# Sheet_Autolabor_Power.net
KiCad netlist of a schematic drawn in Altium Designer
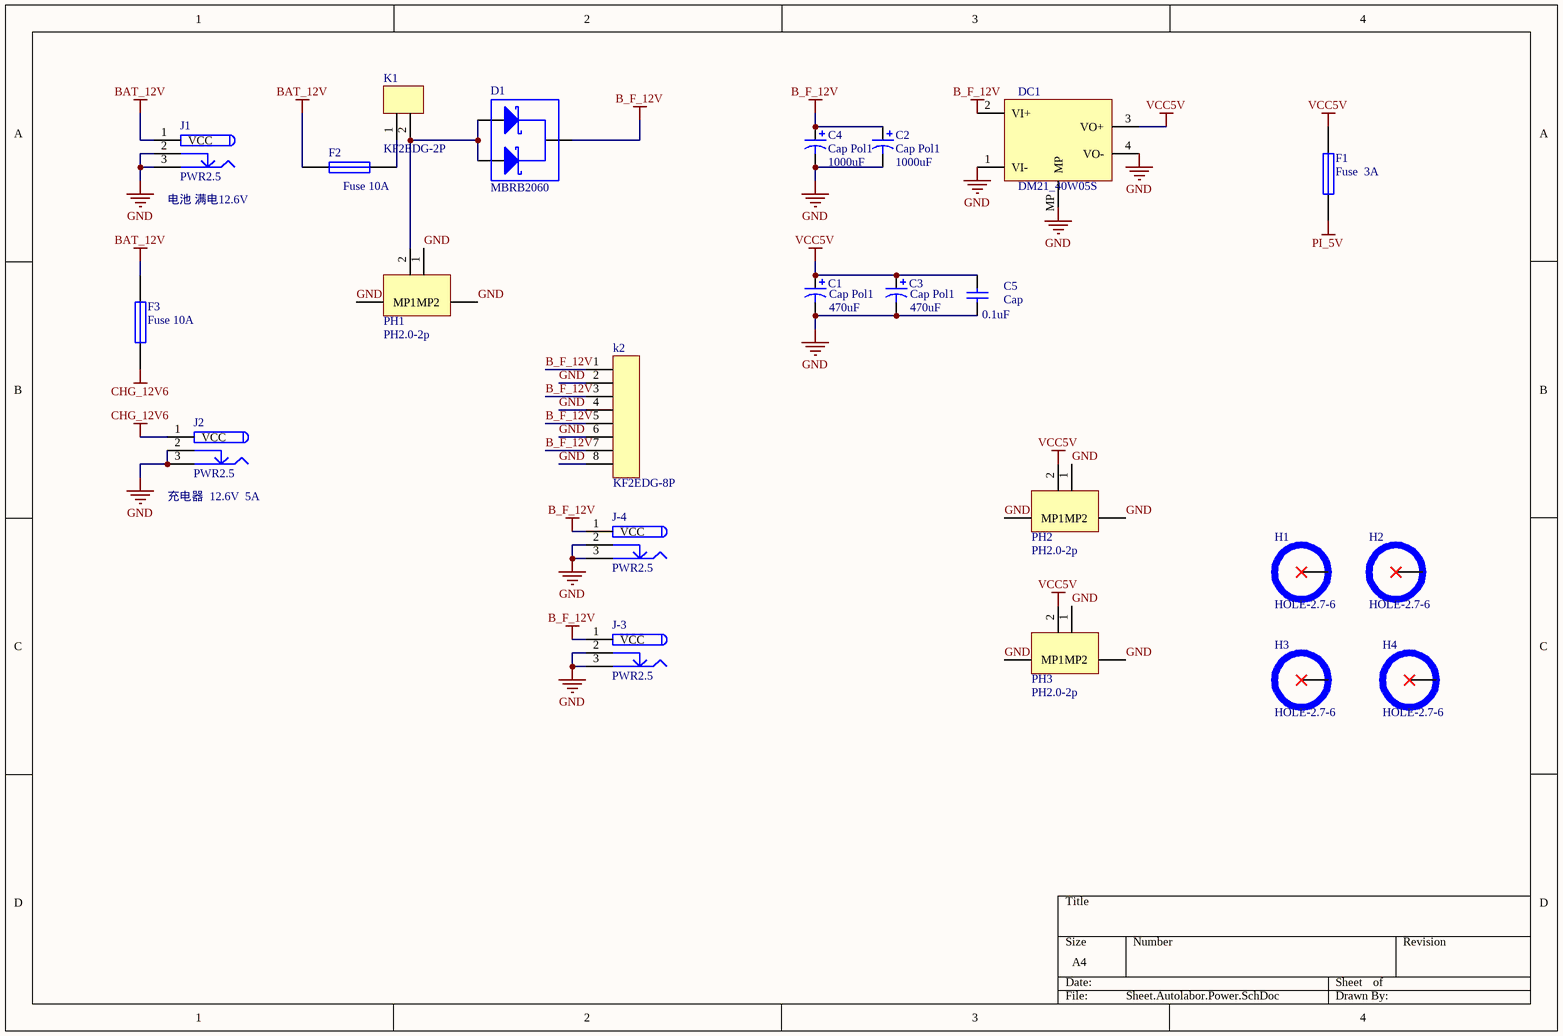
[diagram p0: Sheet.Autolabor.Power.SchDoc]

(export (version "E")
  (design (tool "Eeschema 10.0.6"))
  (components
    (comp (ref "C1")
      (value "Cap Pol1")
      (footprint "CAPAE8883X102M")
      (description "Polarized Capacitor (Radial)")
      (fields (field (name "ALTIUM_VALUE") "470uF") (field (name "PUBLISHER") "Altium Limited"))
      (libsource (lib "Miscellaneous Devices") (part "Cap Pol1"))
    )
    (comp (ref "C2")
      (value "Cap Pol1")
      (footprint "CAPAE108103X102M")
      (description "Polarized Capacitor (Radial)")
      (fields (field (name "ALTIUM_VALUE") "1000uF") (field (name "PUBLISHER") "Altium Limited"))
      (libsource (lib "Miscellaneous Devices") (part "Cap Pol1"))
    )
    (comp (ref "C3")
      (value "Cap Pol1")
      (footprint "CAPAE8883X102M")
      (description "Polarized Capacitor (Radial)")
      (fields (field (name "ALTIUM_VALUE") "470uF") (field (name "PUBLISHER") "Altium Limited"))
      (libsource (lib "Miscellaneous Devices") (part "Cap Pol1"))
    )
    (comp (ref "C4")
      (value "Cap Pol1")
      (footprint "CAPAE108103X102M")
      (description "Polarized Capacitor (Radial)")
      (fields (field (name "ALTIUM_VALUE") "1000uF") (field (name "PUBLISHER") "Altium Limited"))
      (libsource (lib "Miscellaneous Devices") (part "Cap Pol1"))
    )
    (comp (ref "C5")
      (value "Cap")
      (footprint "6-0805_L")
      (description "Capacitor")
      (fields (field (name "ALTIUM_VALUE") "0.1uF") (field (name "PUBLISHER") "Altium Limited"))
      (libsource (lib "Schlib.Autolabor") (part "Cap"))
    )
    (comp (ref "D1")
      (value "MBRB2060")
      (footprint "D2PAK_M")
      (description "Schottky Diode")
      (fields (field (name "PUBLISHER") "Altium Limited"))
      (libsource (lib "Schlib.Autolabor") (part "Schottky-MBRB"))
    )
    (comp (ref "DC1")
      (value "DM21_40W05S")
      (footprint "DM21_40W05S-HOLE")
      (libsource (lib "Schlib.Autolabor") (part "DM21_40W05S"))
    )
    (comp (ref "F1")
      (value "Fuse  3A")
      (footprint "C1206")
      (description "Fuse")
      (fields (field (name "PUBLISHER") "Altium Limited"))
      (libsource (lib "Miscellaneous Devices") (part "Fuse 1"))
    )
    (comp (ref "F2")
      (value "Fuse 10A")
      (footprint "C1206")
      (description "Fuse")
      (fields (field (name "PUBLISHER") "Altium Limited"))
      (libsource (lib "Miscellaneous Devices") (part "Fuse 1"))
    )
    (comp (ref "F3")
      (value "Fuse 10A")
      (footprint "C1206")
      (description "Fuse")
      (fields (field (name "PUBLISHER") "Altium Limited"))
      (libsource (lib "Miscellaneous Devices") (part "Fuse 1"))
    )
    (comp (ref "H1")
      (value "HOLE-2.7-6")
      (footprint "HOLE-2.7-6")
      (libsource (lib "Schlib.Autolabor") (part "HOLE-2.7-6"))
    )
    (comp (ref "H2")
      (value "HOLE-2.7-6")
      (footprint "HOLE-2.7-6")
      (libsource (lib "Schlib.Autolabor") (part "HOLE-2.7-6"))
    )
    (comp (ref "H3")
      (value "HOLE-2.7-6")
      (footprint "HOLE-2.7-6")
      (libsource (lib "Schlib.Autolabor") (part "HOLE-2.7-6"))
    )
    (comp (ref "H4")
      (value "HOLE-2.7-6")
      (footprint "HOLE-2.7-6")
      (libsource (lib "Schlib.Autolabor") (part "HOLE-2.7-6"))
    )
    (comp (ref "J-3")
      (value "PWR2.5")
      (footprint "KLD-0202-SLOT")
      (description "Low Voltage Power Supply Connector")
      (fields (field (name "PUBLISHER") "Altium Limited"))
      (libsource (lib "Schlib.Autolabor") (part "PWR2.5"))
    )
    (comp (ref "J-4")
      (value "PWR2.5")
      (footprint "KLD-0202-SLOT")
      (description "Low Voltage Power Supply Connector")
      (fields (field (name "PUBLISHER") "Altium Limited"))
      (libsource (lib "Schlib.Autolabor") (part "PWR2.5"))
    )
    (comp (ref "J1")
      (value "PWR2.5")
      (footprint "KLD-0202-SLOT")
      (description "Low Voltage Power Supply Connector")
      (fields (field (name "PUBLISHER") "Altium Limited"))
      (libsource (lib "Schlib.Autolabor") (part "PWR2.5"))
    )
    (comp (ref "J2")
      (value "PWR2.5")
      (footprint "KLD-0202-SLOT")
      (description "Low Voltage Power Supply Connector")
      (fields (field (name "PUBLISHER") "Altium Limited"))
      (libsource (lib "Schlib.Autolabor") (part "PWR2.5"))
    )
    (comp (ref "K1")
      (value "KF2EDG-2P")
      (footprint "KF2EDG-3.81-2P")
      (libsource (lib "Schlib.Autolabor") (part "KF2EDG-2P"))
    )
    (comp (ref "k2")
      (value "KF2EDG-8P")
      (footprint "KF2EDG-3.81-8P")
      (libsource (lib "Schlib.Autolabor") (part "KF2EDG-8P"))
    )
    (comp (ref "PH1")
      (value "PH2.0-2p")
      (footprint "PH2.0-LIE-2P")
      (libsource (lib "Schlib.Autolabor") (part "PH2.0-2p"))
    )
    (comp (ref "PH2")
      (value "PH2.0-2p")
      (footprint "PH2.0-LIE-2P")
      (libsource (lib "Schlib.Autolabor") (part "PH2.0-2p"))
    )
    (comp (ref "PH3")
      (value "PH2.0-2p")
      (footprint "PH2.0-LIE-2P")
      (libsource (lib "Schlib.Autolabor") (part "PH2.0-2p"))
    )
  )
  (nets
    (net (code "1") (name "BAT_12V") (class "Default")
      (node (ref "F2") (pin "1") (pinfunction "1_1") (pintype "passive"))
      (node (ref "F3") (pin "2") (pinfunction "2_2") (pintype "passive"))
      (node (ref "J1") (pin "1") (pinfunction "VCC_1") (pintype "passive"))
    )
    (net (code "2") (name "B_F_12V") (class "Default")
      (node (ref "C2") (pin "1") (pinfunction "1_1") (pintype "passive"))
      (node (ref "C4") (pin "1") (pinfunction "1_1") (pintype "passive"))
      (node (ref "D1") (pin "2") (pinfunction "K_2") (pintype "passive"))
      (node (ref "DC1") (pin "2") (pinfunction "VI+_2") (pintype "passive"))
      (node (ref "J-3") (pin "1") (pinfunction "VCC_1") (pintype "passive"))
      (node (ref "J-4") (pin "1") (pinfunction "VCC_1") (pintype "passive"))
      (node (ref "k2") (pin "1") (pinfunction "1_1") (pintype "passive"))
      (node (ref "k2") (pin "3") (pinfunction "3_3") (pintype "passive"))
      (node (ref "k2") (pin "5") (pinfunction "5_5") (pintype "passive"))
      (node (ref "k2") (pin "7") (pinfunction "7_7") (pintype "passive"))
    )
    (net (code "3") (name "CHG_12V6") (class "Default")
      (node (ref "F3") (pin "1") (pinfunction "1_1") (pintype "passive"))
      (node (ref "J2") (pin "1") (pinfunction "VCC_1") (pintype "passive"))
    )
    (net (code "4") (name "GND") (class "Default")
      (node (ref "C1") (pin "2") (pinfunction "2_2") (pintype "passive"))
      (node (ref "C2") (pin "2") (pinfunction "2_2") (pintype "passive"))
      (node (ref "C3") (pin "2") (pinfunction "2_2") (pintype "passive"))
      (node (ref "C4") (pin "2") (pinfunction "2_2") (pintype "passive"))
      (node (ref "C5") (pin "1") (pinfunction "1_1") (pintype "passive"))
      (node (ref "DC1") (pin "1") (pinfunction "VI-_1") (pintype "passive"))
      (node (ref "DC1") (pin "4") (pinfunction "VO-_4") (pintype "passive"))
      (node (ref "DC1") (pin "MP") (pinfunction "MP_MP") (pintype "passive"))
      (node (ref "J-3") (pin "2") (pinfunction "2_2") (pintype "passive"))
      (node (ref "J-3") (pin "3") (pinfunction "3_3") (pintype "passive"))
      (node (ref "J-4") (pin "2") (pinfunction "2_2") (pintype "passive"))
      (node (ref "J-4") (pin "3") (pinfunction "3_3") (pintype "passive"))
      (node (ref "J1") (pin "2") (pinfunction "2_2") (pintype "passive"))
      (node (ref "J1") (pin "3") (pinfunction "3_3") (pintype "passive"))
      (node (ref "J2") (pin "2") (pinfunction "2_2") (pintype "passive"))
      (node (ref "J2") (pin "3") (pinfunction "3_3") (pintype "passive"))
      (node (ref "PH1") (pin "1") (pinfunction "1_1") (pintype "power_in"))
      (node (ref "PH1") (pin "MP1") (pinfunction "MP1_MP1") (pintype "passive"))
      (node (ref "PH1") (pin "MP2") (pinfunction "MP2_MP2") (pintype "passive"))
      (node (ref "PH2") (pin "1") (pinfunction "1_1") (pintype "power_in"))
      (node (ref "PH2") (pin "MP1") (pinfunction "MP1_MP1") (pintype "passive"))
      (node (ref "PH2") (pin "MP2") (pinfunction "MP2_MP2") (pintype "passive"))
      (node (ref "PH3") (pin "1") (pinfunction "1_1") (pintype "power_in"))
      (node (ref "PH3") (pin "MP1") (pinfunction "MP1_MP1") (pintype "passive"))
      (node (ref "PH3") (pin "MP2") (pinfunction "MP2_MP2") (pintype "passive"))
      (node (ref "k2") (pin "2") (pinfunction "2_2") (pintype "passive"))
      (node (ref "k2") (pin "4") (pinfunction "4_4") (pintype "passive"))
      (node (ref "k2") (pin "6") (pinfunction "6_6") (pintype "passive"))
      (node (ref "k2") (pin "8") (pinfunction "8_8") (pintype "passive"))
    )
    (net (code "5") (name "Net-(D1-A-Pad1)") (class "Default")
      (node (ref "D1") (pin "1") (pinfunction "A_1") (pintype "passive"))
      (node (ref "D1") (pin "3") (pinfunction "A_3") (pintype "passive"))
      (node (ref "K1") (pin "2") (pinfunction "2_2") (pintype "passive"))
      (node (ref "PH1") (pin "2") (pinfunction "2_2") (pintype "passive"))
    )
    (net (code "6") (name "Net-(F2-Pad2)") (class "Default")
      (node (ref "F2") (pin "2") (pinfunction "2_2") (pintype "passive"))
      (node (ref "K1") (pin "1") (pinfunction "1_1") (pintype "passive"))
    )
    (net (code "7") (name "PI_5V") (class "Default")
      (node (ref "F1") (pin "1") (pinfunction "1_1") (pintype "passive"))
    )
    (net (code "8") (name "VCC5V") (class "Default")
      (node (ref "C1") (pin "1") (pinfunction "1_1") (pintype "passive"))
      (node (ref "C3") (pin "1") (pinfunction "1_1") (pintype "passive"))
      (node (ref "C5") (pin "2") (pinfunction "2_2") (pintype "passive"))
      (node (ref "DC1") (pin "3") (pinfunction "VO+_3") (pintype "passive"))
      (node (ref "F1") (pin "2") (pinfunction "2_2") (pintype "passive"))
      (node (ref "PH2") (pin "2") (pinfunction "2_2") (pintype "passive"))
      (node (ref "PH3") (pin "2") (pinfunction "2_2") (pintype "passive"))
    )
    (net (code "9") (name "unconnected-(H1-Pad1)") (class "Default")
      (node (ref "H1") (pin "1") (pinfunction "1_1") (pintype "passive+no_connect"))
    )
    (net (code "10") (name "unconnected-(H2-Pad1)") (class "Default")
      (node (ref "H2") (pin "1") (pinfunction "1_1") (pintype "passive+no_connect"))
    )
    (net (code "11") (name "unconnected-(H3-Pad1)") (class "Default")
      (node (ref "H3") (pin "1") (pinfunction "1_1") (pintype "passive+no_connect"))
    )
    (net (code "12") (name "unconnected-(H4-Pad1)") (class "Default")
      (node (ref "H4") (pin "1") (pinfunction "1_1") (pintype "passive+no_connect"))
    )
  )
)
